# RPM_EL311.net
KiCad netlist of a schematic drawn in EAGLE
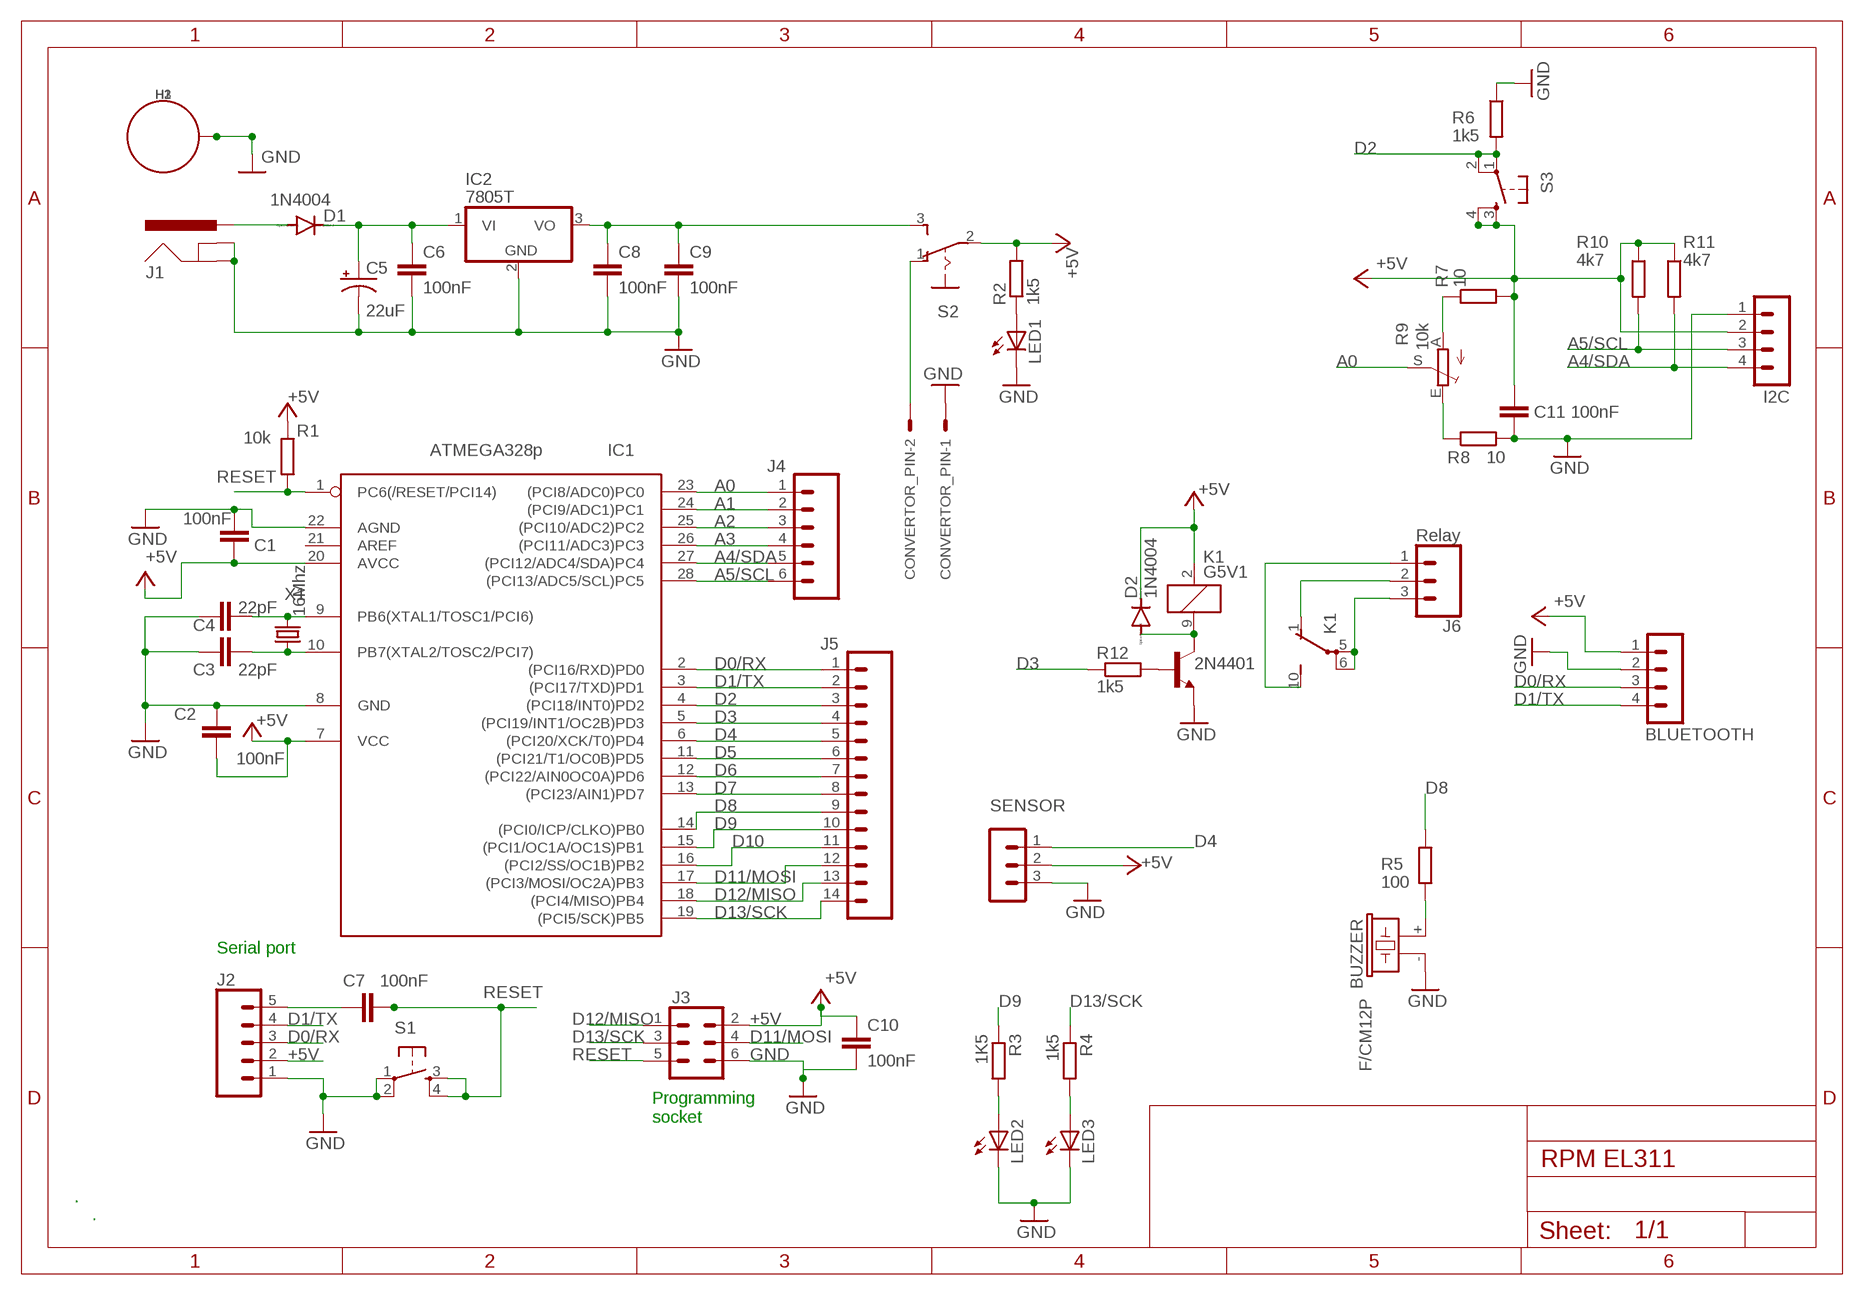
[diagram p0: schematic, sheet 1]

(export (version "E")
  (design (tool "Eeschema 10.0.6"))
  (components
    (comp (ref "2N4401")
      (value "NPN_TRANSISTOR2N3904TO92-EBC")
      (footprint "eagle-import:TO92-EBC")
      (libsource (lib "eagle-import") (part "NPN_TRANSISTORTO92-EBC2N3904"))
    )
    (comp (ref "BLUETOOTH")
      (value "MA04-1")
      (footprint "eagle-import:MA04-1")
      (libsource (lib "eagle-import") (part "MA04-1"))
    )
    (comp (ref "BUZZER")
      (value "F/CM12P")
      (footprint "eagle-import:F_CM12P")
      (libsource (lib "eagle-import") (part "F/CM12P"))
    )
    (comp (ref "C1")
      (value "100nF")
      (footprint "eagle-import:C2.5-2")
      (libsource (lib "eagle-import") (part "C2.5/2"))
    )
    (comp (ref "C2")
      (value "100nF")
      (footprint "eagle-import:C2.5-2")
      (libsource (lib "eagle-import") (part "C2.5/2"))
    )
    (comp (ref "C3")
      (value "22pF")
      (footprint "eagle-import:C2.5-2")
      (libsource (lib "eagle-import") (part "C2.5/2"))
    )
    (comp (ref "C4")
      (value "22pF")
      (footprint "eagle-import:C2.5-2")
      (libsource (lib "eagle-import") (part "C2.5/2"))
    )
    (comp (ref "C5")
      (value "22uF")
      (footprint "eagle-import:E2,5-7")
      (libsource (lib "eagle-import") (part "CPOL-USE2.5-7"))
    )
    (comp (ref "C6")
      (value "100nF")
      (footprint "eagle-import:C2.5-2")
      (libsource (lib "eagle-import") (part "C2.5/2"))
    )
    (comp (ref "C7")
      (value "100nF")
      (footprint "eagle-import:C2.5-2")
      (libsource (lib "eagle-import") (part "C2.5/2"))
    )
    (comp (ref "C8")
      (value "100nF")
      (footprint "eagle-import:C2.5-2")
      (libsource (lib "eagle-import") (part "C2.5/2"))
    )
    (comp (ref "C9")
      (value "100nF")
      (footprint "eagle-import:C2.5-2")
      (libsource (lib "eagle-import") (part "C2.5/2"))
    )
    (comp (ref "C10")
      (value "100nF")
      (footprint "eagle-import:C2.5-2")
      (libsource (lib "eagle-import") (part "C2.5/2"))
    )
    (comp (ref "C11")
      (value "100nF")
      (footprint "eagle-import:C2.5-2")
      (libsource (lib "eagle-import") (part "C2.5/2"))
    )
    (comp (ref "CONVERTOR_PIN")
      (value "5V")
      (footprint "eagle-import:CON-MOLEX_6410-02")
      (libsource (lib "eagle-import") (part "CON-MOLEX_22-?-0227-2021"))
    )
    (comp (ref "D1")
      (value "1N4004")
      (footprint "eagle-import:DO41-10")
      (libsource (lib "eagle-import") (part "diode_210_1N4004"))
    )
    (comp (ref "D2")
      (value "1N4004")
      (footprint "eagle-import:DO41-10")
      (libsource (lib "eagle-import") (part "1N4004"))
    )
    (comp (ref "H1")
      (value "STANDOFF_ELECTRICAL")
      (footprint "eagle-import:STANDOFF-ELECTRICAL")
      (libsource (lib "eagle-import") (part "STANDOFF_ELECTRICAL"))
    )
    (comp (ref "H2")
      (value "STANDOFF_ELECTRICAL")
      (footprint "eagle-import:STANDOFF-ELECTRICAL")
      (libsource (lib "eagle-import") (part "STANDOFF_ELECTRICAL"))
    )
    (comp (ref "H3")
      (value "STANDOFF_ELECTRICAL")
      (footprint "eagle-import:STANDOFF-ELECTRICAL")
      (libsource (lib "eagle-import") (part "STANDOFF_ELECTRICAL"))
    )
    (comp (ref "I2C")
      (value "MA04-1")
      (footprint "eagle-import:MA04-1")
      (libsource (lib "eagle-import") (part "MA04-1"))
    )
    (comp (ref "IC1")
      (value "ATMEGA328p")
      (footprint "eagle-import:DIL28-3")
      (libsource (lib "eagle-import") (part "ATMEGA168PV-10"))
    )
    (comp (ref "IC2")
      (value "7805T")
      (footprint "eagle-import:TO220H")
      (libsource (lib "eagle-import") (part "78T05"))
    )
    (comp (ref "J1")
      (value "EL311-ROBOT_SPARKFUN-CONNECTORS_POWER_JACKPTH")
      (footprint "eagle-import:EL311-ROBOT_SPARKFUN-CONNECTORS_POWER_JACK_PTH")
      (libsource (lib "eagle-import") (part "EL311-ROBOT_SPARKFUN-CONNECTORS_POWER_JACKPTH"))
    )
    (comp (ref "J2")
      (value "CONN_05")
      (footprint "eagle-import:1X05")
      (libsource (lib "eagle-import") (part "CONN_05"))
    )
    (comp (ref "J3")
      (value "FEMALE 2x3")
      (footprint "eagle-import:2X3-SHROUDED")
      (libsource (lib "eagle-import") (part "CONN_03X2SHROUD"))
    )
    (comp (ref "J4")
      (value "CONN_06SILK_FEMALE_PTH")
      (footprint "eagle-import:1X06")
      (libsource (lib "eagle-import") (part "CONN_06SILK_FEMALE_PTH"))
    )
    (comp (ref "J5")
      (value "CONN_14")
      (footprint "eagle-import:1X14")
      (libsource (lib "eagle-import") (part "CONN_14"))
    )
    (comp (ref "J6")
      (value "Relay")
      (footprint "eagle-import:1X03_LONGPADS")
      (libsource (lib "eagle-import") (part "CONN_03LONGPADS"))
    )
    (comp (ref "K1")
      (value "G5V1")
      (footprint "eagle-import:G5V1")
      (fields (field (name "MPN") "G5V-1-DC24"))
      (libsource (lib "eagle-import") (part "G5V1"))
    )
    (comp (ref "LED1")
      (value "LED3MM")
      (footprint "eagle-import:LED3MM")
      (libsource (lib "eagle-import") (part "LED3MM"))
    )
    (comp (ref "LED2")
      (value "LED3MM:1")
      (footprint "eagle-import:LED3MM")
      (libsource (lib "eagle-import") (part "LED?{colon}13MM"))
    )
    (comp (ref "LED3")
      (value "LED3MM:1")
      (footprint "eagle-import:LED3MM")
      (libsource (lib "eagle-import") (part "LED?{colon}13MM"))
    )
    (comp (ref "R1")
      (value "10k")
      (footprint "eagle-import:0207_10")
      (libsource (lib "eagle-import") (part "R-EU_0207/10"))
    )
    (comp (ref "R2")
      (value "1k5")
      (footprint "eagle-import:0207_10")
      (libsource (lib "eagle-import") (part "R-EU_0207/10"))
    )
    (comp (ref "R3")
      (value "1K5")
      (footprint "eagle-import:0207_10")
      (libsource (lib "eagle-import") (part "R-EU_0207/10"))
    )
    (comp (ref "R4")
      (value "1k5")
      (footprint "eagle-import:0207_10")
      (libsource (lib "eagle-import") (part "R-EU_0207/10"))
    )
    (comp (ref "R5")
      (value "100")
      (footprint "eagle-import:0207_10")
      (libsource (lib "eagle-import") (part "R-EU_0207/10"))
    )
    (comp (ref "R6")
      (value "1k5")
      (footprint "eagle-import:0207_10")
      (libsource (lib "eagle-import") (part "R-EU_0207/10"))
    )
    (comp (ref "R7")
      (value "10")
      (footprint "eagle-import:0207_10")
      (libsource (lib "eagle-import") (part "R-EU_0207/10"))
    )
    (comp (ref "R8")
      (value "10")
      (footprint "eagle-import:0207_10")
      (libsource (lib "eagle-import") (part "R-EU_0207/10"))
    )
    (comp (ref "R9")
      (value "10k")
      (footprint "eagle-import:POT_RS3")
      (libsource (lib "eagle-import") (part "POT_TRIM_EU-RS3"))
    )
    (comp (ref "R10")
      (value "4k7")
      (footprint "eagle-import:0207_10")
      (libsource (lib "eagle-import") (part "R-EU_0207/10"))
    )
    (comp (ref "R11")
      (value "4k7")
      (footprint "eagle-import:0207_10")
      (libsource (lib "eagle-import") (part "R-EU_0207/10"))
    )
    (comp (ref "R12")
      (value "1k5")
      (footprint "eagle-import:0207_10")
      (libsource (lib "eagle-import") (part "R-EU_0207/10"))
    )
    (comp (ref "S1")
      (value "EL311-ROBOT_SPARKFUN-ELECTROMECHANICAL_TAC_SWITCHPTH")
      (footprint "eagle-import:EL311-ROBOT_SPARKFUN-ELECTROMECHANICAL_TACTILE-PTH")
      (libsource (lib "eagle-import") (part "EL311-ROBOT_SPARKFUN-ELECTROMECHANICAL_TAC_SWITCHPTH"))
    )
    (comp (ref "S2")
      (value "SWITCH_M251")
      (footprint "eagle-import:SWITCH_M251")
      (libsource (lib "eagle-import") (part "SWITCH_M251"))
    )
    (comp (ref "S3")
      (value "EL311-ROBOT_SPARKFUN-ELECTROMECHANICAL_TAC_SWITCHPTH")
      (footprint "eagle-import:EL311-ROBOT_SPARKFUN-ELECTROMECHANICAL_TACTILE-PTH")
      (libsource (lib "eagle-import") (part "EL311-ROBOT_SPARKFUN-ELECTROMECHANICAL_TAC_SWITCHPTH"))
    )
    (comp (ref "SENSOR")
      (value "MA03-1")
      (footprint "eagle-import:MA03-1")
      (libsource (lib "eagle-import") (part "MA03-1"))
    )
    (comp (ref "X1")
      (value "16Mhz")
      (footprint "eagle-import:HC49U-V")
      (libsource (lib "eagle-import") (part "CRYSTALHC49U-V"))
    )
  )
  (nets
    (net (code "1") (name "+5V") (class "Default")
      (node (ref "BLUETOOTH") (pin "1") (pinfunction "1_1") (pintype "passive"))
      (node (ref "C1") (pin "2") (pinfunction "2_2") (pintype "passive"))
      (node (ref "C10") (pin "1") (pinfunction "1_1") (pintype "passive"))
      (node (ref "C11") (pin "1") (pinfunction "1_1") (pintype "passive"))
      (node (ref "C2") (pin "2") (pinfunction "2_2") (pintype "passive"))
      (node (ref "D2") (pin "C") (pinfunction "C_C") (pintype "passive"))
      (node (ref "I2C") (pin "2") (pinfunction "2_2") (pintype "passive"))
      (node (ref "IC1") (pin "20") (pinfunction "AVCC_20") (pintype "bidirectional"))
      (node (ref "IC1") (pin "7") (pinfunction "VCC_7") (pintype "bidirectional"))
      (node (ref "J2") (pin "2") (pinfunction "2_2") (pintype "passive"))
      (node (ref "J3") (pin "2") (pinfunction "2_2") (pintype "bidirectional"))
      (node (ref "K1") (pin "2") (pinfunction "1_2") (pintype "passive"))
      (node (ref "R1") (pin "1") (pinfunction "1_1") (pintype "passive"))
      (node (ref "R10") (pin "1") (pinfunction "1_1") (pintype "passive"))
      (node (ref "R11") (pin "1") (pinfunction "1_1") (pintype "passive"))
      (node (ref "R2") (pin "2") (pinfunction "2_2") (pintype "passive"))
      (node (ref "R7") (pin "2") (pinfunction "2_2") (pintype "passive"))
      (node (ref "S2") (pin "2") (pinfunction "P_2") (pintype "passive"))
      (node (ref "S3") (pin "3") (pinfunction "3_3") (pintype "passive"))
      (node (ref "S3") (pin "4") (pinfunction "4_4") (pintype "passive"))
      (node (ref "SENSOR") (pin "2") (pinfunction "2_2") (pintype "passive"))
    )
    (net (code "2") (name "/A0") (class "Default")
      (node (ref "IC1") (pin "23") (pinfunction "(PCI8/ADC0)PC0_23") (pintype "bidirectional"))
      (node (ref "J4") (pin "1") (pinfunction "1_1") (pintype "passive"))
      (node (ref "R9") (pin "S") (pinfunction "S_S") (pintype "passive"))
    )
    (net (code "3") (name "/A1") (class "Default")
      (node (ref "IC1") (pin "24") (pinfunction "(PCI9/ADC1)PC1_24") (pintype "bidirectional"))
      (node (ref "J4") (pin "2") (pinfunction "2_2") (pintype "passive"))
    )
    (net (code "4") (name "/A2") (class "Default")
      (node (ref "IC1") (pin "25") (pinfunction "(PCI10/ADC2)PC2_25") (pintype "bidirectional"))
      (node (ref "J4") (pin "3") (pinfunction "3_3") (pintype "passive"))
    )
    (net (code "5") (name "/A3") (class "Default")
      (node (ref "IC1") (pin "26") (pinfunction "(PCI11/ADC3)PC3_26") (pintype "bidirectional"))
      (node (ref "J4") (pin "4") (pinfunction "4_4") (pintype "passive"))
    )
    (net (code "6") (name "/A4{slash}SDA") (class "Default")
      (node (ref "I2C") (pin "4") (pinfunction "4_4") (pintype "passive"))
      (node (ref "IC1") (pin "27") (pinfunction "(PCI12/ADC4/SDA)PC4_27") (pintype "bidirectional"))
      (node (ref "J4") (pin "5") (pinfunction "5_5") (pintype "passive"))
      (node (ref "R11") (pin "2") (pinfunction "2_2") (pintype "passive"))
    )
    (net (code "7") (name "/A5{slash}SCL") (class "Default")
      (node (ref "I2C") (pin "3") (pinfunction "3_3") (pintype "passive"))
      (node (ref "IC1") (pin "28") (pinfunction "(PCI13/ADC5/SCL)PC5_28") (pintype "bidirectional"))
      (node (ref "J4") (pin "6") (pinfunction "6_6") (pintype "passive"))
      (node (ref "R10") (pin "2") (pinfunction "2_2") (pintype "passive"))
    )
    (net (code "8") (name "/D0{slash}RX") (class "Default")
      (node (ref "BLUETOOTH") (pin "3") (pinfunction "3_3") (pintype "passive"))
      (node (ref "IC1") (pin "2") (pinfunction "(PCI16/RXD)PD0_2") (pintype "bidirectional"))
      (node (ref "J2") (pin "3") (pinfunction "3_3") (pintype "passive"))
      (node (ref "J5") (pin "1") (pinfunction "1_1") (pintype "passive"))
    )
    (net (code "9") (name "/D1{slash}TX") (class "Default")
      (node (ref "BLUETOOTH") (pin "4") (pinfunction "4_4") (pintype "passive"))
      (node (ref "IC1") (pin "3") (pinfunction "(PCI17/TXD)PD1_3") (pintype "bidirectional"))
      (node (ref "J2") (pin "4") (pinfunction "4_4") (pintype "passive"))
      (node (ref "J5") (pin "2") (pinfunction "2_2") (pintype "passive"))
    )
    (net (code "10") (name "/D2") (class "Default")
      (node (ref "IC1") (pin "4") (pinfunction "(PCI18/INT0)PD2_4") (pintype "bidirectional"))
      (node (ref "J5") (pin "3") (pinfunction "3_3") (pintype "passive"))
      (node (ref "R6") (pin "2") (pinfunction "2_2") (pintype "passive"))
      (node (ref "S3") (pin "1") (pinfunction "1_1") (pintype "passive"))
      (node (ref "S3") (pin "2") (pinfunction "2_2") (pintype "passive"))
    )
    (net (code "11") (name "/D3") (class "Default")
      (node (ref "IC1") (pin "5") (pinfunction "(PCI19/INT1/OC2B)PD3_5") (pintype "bidirectional"))
      (node (ref "J5") (pin "4") (pinfunction "4_4") (pintype "passive"))
      (node (ref "R12") (pin "1") (pinfunction "1_1") (pintype "passive"))
    )
    (net (code "12") (name "/D4") (class "Default")
      (node (ref "IC1") (pin "6") (pinfunction "(PCI20/XCK/T0)PD4_6") (pintype "bidirectional"))
      (node (ref "J5") (pin "5") (pinfunction "5_5") (pintype "passive"))
      (node (ref "SENSOR") (pin "1") (pinfunction "1_1") (pintype "passive"))
    )
    (net (code "13") (name "/D5") (class "Default")
      (node (ref "IC1") (pin "11") (pinfunction "(PCI21/T1/OC0B)PD5_11") (pintype "bidirectional"))
      (node (ref "J5") (pin "6") (pinfunction "6_6") (pintype "passive"))
    )
    (net (code "14") (name "/D6") (class "Default")
      (node (ref "IC1") (pin "12") (pinfunction "(PCI22/AIN0OC0A)PD6_12") (pintype "bidirectional"))
      (node (ref "J5") (pin "7") (pinfunction "7_7") (pintype "passive"))
    )
    (net (code "15") (name "/D7") (class "Default")
      (node (ref "IC1") (pin "13") (pinfunction "(PCI23/AIN1)PD7_13") (pintype "bidirectional"))
      (node (ref "J5") (pin "8") (pinfunction "8_8") (pintype "passive"))
    )
    (net (code "16") (name "/D8") (class "Default")
      (node (ref "IC1") (pin "14") (pinfunction "(PCI0/ICP/CLKO)PB0_14") (pintype "bidirectional"))
      (node (ref "J5") (pin "9") (pinfunction "9_9") (pintype "passive"))
      (node (ref "R5") (pin "1") (pinfunction "1_1") (pintype "passive"))
    )
    (net (code "17") (name "/D9") (class "Default")
      (node (ref "IC1") (pin "15") (pinfunction "(PCI1/OC1A/OC1S)PB1_15") (pintype "bidirectional"))
      (node (ref "J5") (pin "10") (pinfunction "10_10") (pintype "passive"))
      (node (ref "R3") (pin "1") (pinfunction "1_1") (pintype "passive"))
    )
    (net (code "18") (name "/D10") (class "Default")
      (node (ref "IC1") (pin "16") (pinfunction "(PCI2/SS/OC1B)PB2_16") (pintype "bidirectional"))
      (node (ref "J5") (pin "11") (pinfunction "11_11") (pintype "passive"))
    )
    (net (code "19") (name "/D11{slash}MOSI") (class "Default")
      (node (ref "IC1") (pin "17") (pinfunction "(PCI3/MOSI/OC2A)PB3_17") (pintype "bidirectional"))
      (node (ref "J3") (pin "4") (pinfunction "4_4") (pintype "bidirectional"))
      (node (ref "J5") (pin "12") (pinfunction "12_12") (pintype "passive"))
    )
    (net (code "20") (name "/D12{slash}MISO") (class "Default")
      (node (ref "IC1") (pin "18") (pinfunction "(PCI4/MISO)PB4_18") (pintype "bidirectional"))
      (node (ref "J3") (pin "1") (pinfunction "1_1") (pintype "bidirectional"))
      (node (ref "J5") (pin "13") (pinfunction "13_13") (pintype "passive"))
    )
    (net (code "21") (name "/D13{slash}SCK") (class "Default")
      (node (ref "IC1") (pin "19") (pinfunction "(PCI5/SCK)PB5_19") (pintype "bidirectional"))
      (node (ref "J3") (pin "3") (pinfunction "3_3") (pintype "bidirectional"))
      (node (ref "J5") (pin "14") (pinfunction "14_14") (pintype "passive"))
      (node (ref "R4") (pin "1") (pinfunction "1_1") (pintype "passive"))
    )
    (net (code "22") (name "/RESET") (class "Default")
      (node (ref "C7") (pin "2") (pinfunction "2_2") (pintype "passive"))
      (node (ref "IC1") (pin "1") (pinfunction "PC6(/RESET/PCI14)_1") (pintype "bidirectional"))
      (node (ref "J3") (pin "5") (pinfunction "5_5") (pintype "bidirectional"))
      (node (ref "R1") (pin "2") (pinfunction "2_2") (pintype "passive"))
      (node (ref "S1") (pin "3") (pinfunction "3_3") (pintype "passive"))
      (node (ref "S1") (pin "4") (pinfunction "4_4") (pintype "passive"))
    )
    (net (code "23") (name "GND") (class "Default")
      (node (ref "2N4401") (pin "E") (pinfunction "E_E") (pintype "passive"))
      (node (ref "BLUETOOTH") (pin "2") (pinfunction "2_2") (pintype "passive"))
      (node (ref "BUZZER") (pin "-") (pinfunction "2_-") (pintype "passive"))
      (node (ref "C1") (pin "1") (pinfunction "1_1") (pintype "passive"))
      (node (ref "C10") (pin "2") (pinfunction "2_2") (pintype "passive"))
      (node (ref "C11") (pin "2") (pinfunction "2_2") (pintype "passive"))
      (node (ref "C2") (pin "1") (pinfunction "1_1") (pintype "passive"))
      (node (ref "C3") (pin "1") (pinfunction "1_1") (pintype "passive"))
      (node (ref "C4") (pin "1") (pinfunction "1_1") (pintype "passive"))
      (node (ref "C5") (pin "-") (pinfunction "-_-") (pintype "passive"))
      (node (ref "C6") (pin "2") (pinfunction "2_2") (pintype "passive"))
      (node (ref "C8") (pin "2") (pinfunction "2_2") (pintype "passive"))
      (node (ref "C9") (pin "2") (pinfunction "2_2") (pintype "passive"))
      (node (ref "CONVERTOR_PIN") (pin "1") (pinfunction "S_1") (pintype "passive"))
      (node (ref "H1") (pin "P1") (pinfunction "P$1_P1") (pintype "bidirectional"))
      (node (ref "H2") (pin "P1") (pinfunction "P$1_P1") (pintype "bidirectional"))
      (node (ref "H3") (pin "P1") (pinfunction "P$1_P1") (pintype "bidirectional"))
      (node (ref "I2C") (pin "1") (pinfunction "1_1") (pintype "passive"))
      (node (ref "IC1") (pin "22") (pinfunction "AGND_22") (pintype "bidirectional"))
      (node (ref "IC1") (pin "8") (pinfunction "GND_8") (pintype "bidirectional"))
      (node (ref "IC2") (pin "2") (pinfunction "GND_2") (pintype "passive"))
      (node (ref "J1") (pin "GND") (pinfunction "GND_GND") (pintype "bidirectional"))
      (node (ref "J1") (pin "GNDBREAK") (pinfunction "GNDBREAK_GNDBREAK") (pintype "bidirectional"))
      (node (ref "J2") (pin "1") (pinfunction "1_1") (pintype "passive"))
      (node (ref "J3") (pin "6") (pinfunction "6_6") (pintype "bidirectional"))
      (node (ref "LED1") (pin "K") (pinfunction "C_K") (pintype "passive"))
      (node (ref "LED2") (pin "K") (pinfunction "C_K") (pintype "passive"))
      (node (ref "LED3") (pin "K") (pinfunction "C_K") (pintype "passive"))
      (node (ref "R6") (pin "1") (pinfunction "1_1") (pintype "passive"))
      (node (ref "R8") (pin "2") (pinfunction "2_2") (pintype "passive"))
      (node (ref "S1") (pin "1") (pinfunction "1_1") (pintype "passive"))
      (node (ref "S1") (pin "2") (pinfunction "2_2") (pintype "passive"))
      (node (ref "SENSOR") (pin "3") (pinfunction "3_3") (pintype "passive"))
    )
    (net (code "24") (name "Net-(2N4401-PadB)") (class "Default")
      (node (ref "2N4401") (pin "B") (pinfunction "B_B") (pintype "passive"))
      (node (ref "R12") (pin "2") (pinfunction "2_2") (pintype "passive"))
    )
    (net (code "25") (name "Net-(BUZZER-1)") (class "Default")
      (node (ref "BUZZER") (pin "+") (pinfunction "1_+") (pintype "passive"))
      (node (ref "R5") (pin "2") (pinfunction "2_2") (pintype "passive"))
    )
    (net (code "26") (name "Net-(C7-Pad1)") (class "Default")
      (node (ref "C7") (pin "1") (pinfunction "1_1") (pintype "passive"))
      (node (ref "J2") (pin "5") (pinfunction "5_5") (pintype "passive"))
    )
    (net (code "27") (name "Net-(CONVERTOR_PINB-S)") (class "Default")
      (node (ref "CONVERTOR_PIN") (pin "2") (pinfunction "S_2") (pintype "passive"))
      (node (ref "S2") (pin "1") (pinfunction "O_1") (pintype "passive"))
    )
    (net (code "28") (name "Net-(D1-PadA)") (class "Default")
      (node (ref "D1") (pin "A") (pinfunction "A_A") (pintype "passive"))
      (node (ref "J1") (pin "PWR") (pinfunction "PWR_PWR") (pintype "bidirectional"))
    )
    (net (code "29") (name "Net-(IC1-PB6(XTAL1{slash}TOSC1{slash}PCI6))") (class "Default")
      (node (ref "C4") (pin "2") (pinfunction "2_2") (pintype "passive"))
      (node (ref "IC1") (pin "9") (pinfunction "PB6(XTAL1/TOSC1/PCI6)_9") (pintype "bidirectional"))
      (node (ref "X1") (pin "2") (pinfunction "2_2") (pintype "passive"))
    )
    (net (code "30") (name "Net-(IC1-PB7(XTAL2{slash}TOSC2{slash}PCI7))") (class "Default")
      (node (ref "C3") (pin "2") (pinfunction "2_2") (pintype "passive"))
      (node (ref "IC1") (pin "10") (pinfunction "PB7(XTAL2/TOSC2/PCI7)_10") (pintype "bidirectional"))
      (node (ref "X1") (pin "1") (pinfunction "1_1") (pintype "passive"))
    )
    (net (code "31") (name "Net-(IC2-VI)") (class "Default")
      (node (ref "C5") (pin "+") (pinfunction "+_+") (pintype "passive"))
      (node (ref "C6") (pin "1") (pinfunction "1_1") (pintype "passive"))
      (node (ref "D1") (pin "C") (pinfunction "C_C") (pintype "passive"))
      (node (ref "IC2") (pin "1") (pinfunction "VI_1") (pintype "input"))
    )
    (net (code "32") (name "Net-(IC2-VO)") (class "Default")
      (node (ref "C8") (pin "1") (pinfunction "1_1") (pintype "passive"))
      (node (ref "C9") (pin "1") (pinfunction "1_1") (pintype "passive"))
      (node (ref "IC2") (pin "3") (pinfunction "VO_3") (pintype "passive"))
      (node (ref "S2") (pin "3") (pinfunction "S_3") (pintype "passive"))
    )
    (net (code "33") (name "Net-(J6-Pad3)") (class "Default")
      (node (ref "J6") (pin "3") (pinfunction "3_3") (pintype "passive"))
      (node (ref "K1") (pin "5") (pinfunction "P_5") (pintype "passive"))
      (node (ref "K1") (pin "6") (pinfunction "P_6") (pintype "passive"))
    )
    (net (code "34") (name "Net-(K1A-2)") (class "Default")
      (node (ref "2N4401") (pin "C") (pinfunction "C_C") (pintype "passive"))
      (node (ref "D2") (pin "A") (pinfunction "A_A") (pintype "passive"))
      (node (ref "K1") (pin "9") (pinfunction "2_9") (pintype "passive"))
    )
    (net (code "35") (name "Net-(K1B-O)") (class "Default")
      (node (ref "J6") (pin "2") (pinfunction "2_2") (pintype "passive"))
      (node (ref "K1") (pin "1") (pinfunction "O_1") (pintype "passive"))
    )
    (net (code "36") (name "Net-(K1B-S)") (class "Default")
      (node (ref "J6") (pin "1") (pinfunction "1_1") (pintype "passive"))
      (node (ref "K1") (pin "10") (pinfunction "S_10") (pintype "passive"))
    )
    (net (code "37") (name "Net-(LED1-PadA)") (class "Default")
      (node (ref "LED1") (pin "A") (pinfunction "A_A") (pintype "passive"))
      (node (ref "R2") (pin "1") (pinfunction "1_1") (pintype "passive"))
    )
    (net (code "38") (name "Net-(LED2-PadA)") (class "Default")
      (node (ref "LED2") (pin "A") (pinfunction "A_A") (pintype "passive"))
      (node (ref "R3") (pin "2") (pinfunction "2_2") (pintype "passive"))
    )
    (net (code "39") (name "Net-(LED3-PadA)") (class "Default")
      (node (ref "LED3") (pin "A") (pinfunction "A_A") (pintype "passive"))
      (node (ref "R4") (pin "2") (pinfunction "2_2") (pintype "passive"))
    )
    (net (code "40") (name "Net-(R7-Pad1)") (class "Default")
      (node (ref "R7") (pin "1") (pinfunction "1_1") (pintype "passive"))
      (node (ref "R9") (pin "A") (pinfunction "A_A") (pintype "passive"))
    )
    (net (code "41") (name "Net-(R8-Pad1)") (class "Default")
      (node (ref "R8") (pin "1") (pinfunction "1_1") (pintype "passive"))
      (node (ref "R9") (pin "E") (pinfunction "E_E") (pintype "passive"))
    )
    (net (code "42") (name "unconnected-(IC1-AREF-Pad21)") (class "Default")
      (node (ref "IC1") (pin "21") (pinfunction "AREF_21") (pintype "bidirectional"))
    )
  )
)
